# FPGA2_POWER.net
KiCad netlist of a schematic drawn in Altium Designer
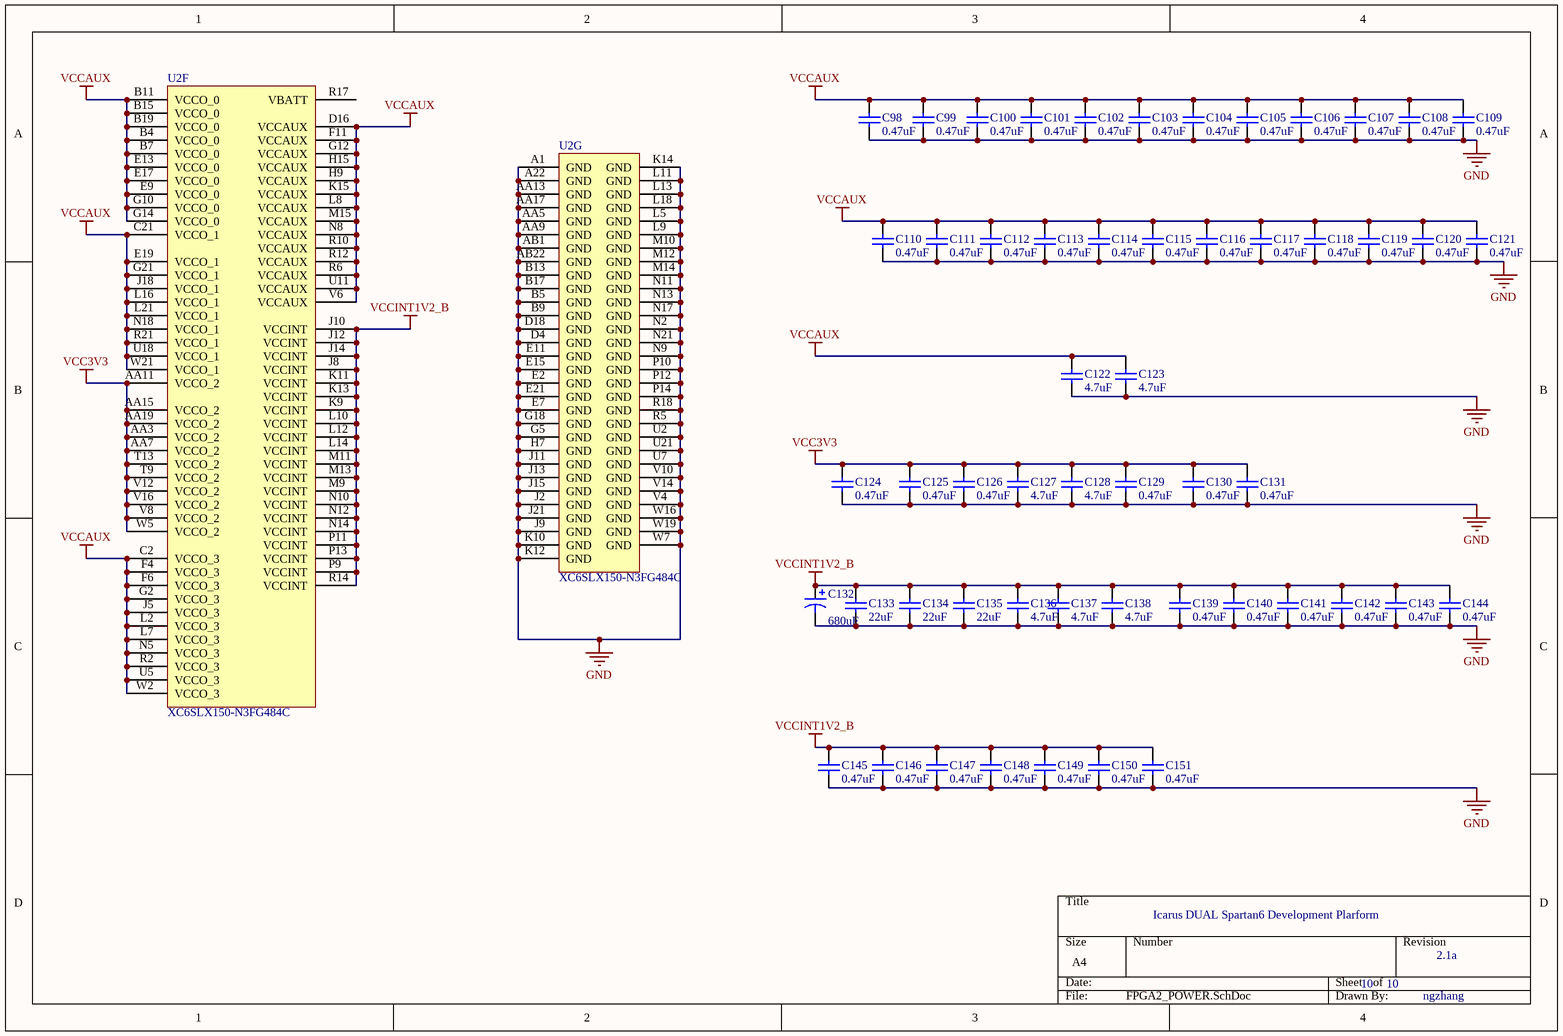
[diagram p0: FPGA2_POWER.SchDoc]

(export (version "E")
  (design (tool "Eeschema 10.0.6"))
  (components
    (comp (ref "C98")
      (value "0.47uF")
      (footprint "0402")
      (description "Capacitor (Semiconductor SIM Model)")
      (fields (field (name "PUBLISHER") "Altium Limited"))
      (libsource (lib "Miscellaneous Devices") (part "Cap Semi"))
    )
    (comp (ref "C99")
      (value "0.47uF")
      (footprint "0402")
      (description "Capacitor (Semiconductor SIM Model)")
      (fields (field (name "PUBLISHER") "Altium Limited"))
      (libsource (lib "Miscellaneous Devices") (part "Cap Semi"))
    )
    (comp (ref "C100")
      (value "0.47uF")
      (footprint "0402")
      (description "Capacitor (Semiconductor SIM Model)")
      (fields (field (name "PUBLISHER") "Altium Limited"))
      (libsource (lib "Miscellaneous Devices") (part "Cap Semi"))
    )
    (comp (ref "C101")
      (value "0.47uF")
      (footprint "0402")
      (description "Capacitor (Semiconductor SIM Model)")
      (fields (field (name "PUBLISHER") "Altium Limited"))
      (libsource (lib "Miscellaneous Devices") (part "Cap Semi"))
    )
    (comp (ref "C102")
      (value "0.47uF")
      (footprint "0402")
      (description "Capacitor (Semiconductor SIM Model)")
      (fields (field (name "PUBLISHER") "Altium Limited"))
      (libsource (lib "Miscellaneous Devices") (part "Cap Semi"))
    )
    (comp (ref "C103")
      (value "0.47uF")
      (footprint "0402")
      (description "Capacitor (Semiconductor SIM Model)")
      (fields (field (name "PUBLISHER") "Altium Limited"))
      (libsource (lib "Miscellaneous Devices") (part "Cap Semi"))
    )
    (comp (ref "C104")
      (value "0.47uF")
      (footprint "0402")
      (description "Capacitor (Semiconductor SIM Model)")
      (fields (field (name "PUBLISHER") "Altium Limited"))
      (libsource (lib "Miscellaneous Devices") (part "Cap Semi"))
    )
    (comp (ref "C105")
      (value "0.47uF")
      (footprint "0402")
      (description "Capacitor (Semiconductor SIM Model)")
      (fields (field (name "PUBLISHER") "Altium Limited"))
      (libsource (lib "Miscellaneous Devices") (part "Cap Semi"))
    )
    (comp (ref "C106")
      (value "0.47uF")
      (footprint "0402")
      (description "Capacitor (Semiconductor SIM Model)")
      (fields (field (name "PUBLISHER") "Altium Limited"))
      (libsource (lib "Miscellaneous Devices") (part "Cap Semi"))
    )
    (comp (ref "C107")
      (value "0.47uF")
      (footprint "0402")
      (description "Capacitor (Semiconductor SIM Model)")
      (fields (field (name "PUBLISHER") "Altium Limited"))
      (libsource (lib "Miscellaneous Devices") (part "Cap Semi"))
    )
    (comp (ref "C108")
      (value "0.47uF")
      (footprint "0402")
      (description "Capacitor (Semiconductor SIM Model)")
      (fields (field (name "PUBLISHER") "Altium Limited"))
      (libsource (lib "Miscellaneous Devices") (part "Cap Semi"))
    )
    (comp (ref "C109")
      (value "0.47uF")
      (footprint "0402")
      (description "Capacitor (Semiconductor SIM Model)")
      (fields (field (name "PUBLISHER") "Altium Limited"))
      (libsource (lib "Miscellaneous Devices") (part "Cap Semi"))
    )
    (comp (ref "C110")
      (value "0.47uF")
      (footprint "0402")
      (description "Capacitor (Semiconductor SIM Model)")
      (fields (field (name "PUBLISHER") "Altium Limited"))
      (libsource (lib "Miscellaneous Devices") (part "Cap Semi"))
    )
    (comp (ref "C111")
      (value "0.47uF")
      (footprint "0402")
      (description "Capacitor (Semiconductor SIM Model)")
      (fields (field (name "PUBLISHER") "Altium Limited"))
      (libsource (lib "Miscellaneous Devices") (part "Cap Semi"))
    )
    (comp (ref "C112")
      (value "0.47uF")
      (footprint "0402")
      (description "Capacitor (Semiconductor SIM Model)")
      (fields (field (name "PUBLISHER") "Altium Limited"))
      (libsource (lib "Miscellaneous Devices") (part "Cap Semi"))
    )
    (comp (ref "C113")
      (value "0.47uF")
      (footprint "0402")
      (description "Capacitor (Semiconductor SIM Model)")
      (fields (field (name "PUBLISHER") "Altium Limited"))
      (libsource (lib "Miscellaneous Devices") (part "Cap Semi"))
    )
    (comp (ref "C114")
      (value "0.47uF")
      (footprint "0402")
      (description "Capacitor (Semiconductor SIM Model)")
      (fields (field (name "PUBLISHER") "Altium Limited"))
      (libsource (lib "Miscellaneous Devices") (part "Cap Semi"))
    )
    (comp (ref "C115")
      (value "0.47uF")
      (footprint "0402")
      (description "Capacitor (Semiconductor SIM Model)")
      (fields (field (name "PUBLISHER") "Altium Limited"))
      (libsource (lib "Miscellaneous Devices") (part "Cap Semi"))
    )
    (comp (ref "C116")
      (value "0.47uF")
      (footprint "0402")
      (description "Capacitor (Semiconductor SIM Model)")
      (fields (field (name "PUBLISHER") "Altium Limited"))
      (libsource (lib "Miscellaneous Devices") (part "Cap Semi"))
    )
    (comp (ref "C117")
      (value "0.47uF")
      (footprint "0402")
      (description "Capacitor (Semiconductor SIM Model)")
      (fields (field (name "PUBLISHER") "Altium Limited"))
      (libsource (lib "Miscellaneous Devices") (part "Cap Semi"))
    )
    (comp (ref "C118")
      (value "0.47uF")
      (footprint "0402")
      (description "Capacitor (Semiconductor SIM Model)")
      (fields (field (name "PUBLISHER") "Altium Limited"))
      (libsource (lib "Miscellaneous Devices") (part "Cap Semi"))
    )
    (comp (ref "C119")
      (value "0.47uF")
      (footprint "0402")
      (description "Capacitor (Semiconductor SIM Model)")
      (fields (field (name "PUBLISHER") "Altium Limited"))
      (libsource (lib "Miscellaneous Devices") (part "Cap Semi"))
    )
    (comp (ref "C120")
      (value "0.47uF")
      (footprint "0402")
      (description "Capacitor (Semiconductor SIM Model)")
      (fields (field (name "PUBLISHER") "Altium Limited"))
      (libsource (lib "Miscellaneous Devices") (part "Cap Semi"))
    )
    (comp (ref "C121")
      (value "0.47uF")
      (footprint "0402")
      (description "Capacitor (Semiconductor SIM Model)")
      (fields (field (name "PUBLISHER") "Altium Limited"))
      (libsource (lib "Miscellaneous Devices") (part "Cap Semi"))
    )
    (comp (ref "C122")
      (value "4.7uF")
      (footprint "C0805")
      (description "Capacitor (Semiconductor SIM Model)")
      (fields (field (name "PUBLISHER") "Altium Limited"))
      (libsource (lib "Miscellaneous Devices") (part "Cap Semi"))
    )
    (comp (ref "C123")
      (value "4.7uF")
      (footprint "C0805")
      (description "Capacitor (Semiconductor SIM Model)")
      (fields (field (name "PUBLISHER") "Altium Limited"))
      (libsource (lib "Miscellaneous Devices") (part "Cap Semi"))
    )
    (comp (ref "C124")
      (value "0.47uF")
      (footprint "0402")
      (description "Capacitor (Semiconductor SIM Model)")
      (fields (field (name "PUBLISHER") "Altium Limited"))
      (libsource (lib "Miscellaneous Devices") (part "Cap Semi"))
    )
    (comp (ref "C125")
      (value "0.47uF")
      (footprint "0402")
      (description "Capacitor (Semiconductor SIM Model)")
      (fields (field (name "PUBLISHER") "Altium Limited"))
      (libsource (lib "Miscellaneous Devices") (part "Cap Semi"))
    )
    (comp (ref "C126")
      (value "0.47uF")
      (footprint "0402")
      (description "Capacitor (Semiconductor SIM Model)")
      (fields (field (name "PUBLISHER") "Altium Limited"))
      (libsource (lib "Miscellaneous Devices") (part "Cap Semi"))
    )
    (comp (ref "C127")
      (value "4.7uF")
      (footprint "C0805")
      (description "Capacitor (Semiconductor SIM Model)")
      (fields (field (name "PUBLISHER") "Altium Limited"))
      (libsource (lib "Miscellaneous Devices") (part "Cap Semi"))
    )
    (comp (ref "C128")
      (value "4.7uF")
      (footprint "C0805")
      (description "Capacitor (Semiconductor SIM Model)")
      (fields (field (name "PUBLISHER") "Altium Limited"))
      (libsource (lib "Miscellaneous Devices") (part "Cap Semi"))
    )
    (comp (ref "C129")
      (value "0.47uF")
      (footprint "0402")
      (description "Capacitor (Semiconductor SIM Model)")
      (fields (field (name "PUBLISHER") "Altium Limited"))
      (libsource (lib "Miscellaneous Devices") (part "Cap Semi"))
    )
    (comp (ref "C130")
      (value "0.47uF")
      (footprint "0402")
      (description "Capacitor (Semiconductor SIM Model)")
      (fields (field (name "PUBLISHER") "Altium Limited"))
      (libsource (lib "Miscellaneous Devices") (part "Cap Semi"))
    )
    (comp (ref "C131")
      (value "0.47uF")
      (footprint "0402")
      (description "Capacitor (Semiconductor SIM Model)")
      (fields (field (name "PUBLISHER") "Altium Limited"))
      (libsource (lib "Miscellaneous Devices") (part "Cap Semi"))
    )
    (comp (ref "C132")
      (value "680uF")
      (footprint "D")
      (description "Polarized Capacitor (Surface Mount)")
      (fields (field (name "PUBLISHER") "Altium Limited"))
      (libsource (lib "Miscellaneous Devices") (part "Cap Pol3"))
    )
    (comp (ref "C133")
      (value "22uF")
      (footprint "C1206")
      (description "Capacitor (Semiconductor SIM Model)")
      (fields (field (name "PUBLISHER") "Altium Limited"))
      (libsource (lib "Miscellaneous Devices") (part "Cap Semi"))
    )
    (comp (ref "C134")
      (value "22uF")
      (footprint "C1206")
      (description "Capacitor (Semiconductor SIM Model)")
      (fields (field (name "PUBLISHER") "Altium Limited"))
      (libsource (lib "Miscellaneous Devices") (part "Cap Semi"))
    )
    (comp (ref "C135")
      (value "22uF")
      (footprint "C1206")
      (description "Capacitor (Semiconductor SIM Model)")
      (fields (field (name "PUBLISHER") "Altium Limited"))
      (libsource (lib "Miscellaneous Devices") (part "Cap Semi"))
    )
    (comp (ref "C136")
      (value "4.7uF")
      (footprint "C0805")
      (description "Capacitor (Semiconductor SIM Model)")
      (fields (field (name "PUBLISHER") "Altium Limited"))
      (libsource (lib "Miscellaneous Devices") (part "Cap Semi"))
    )
    (comp (ref "C137")
      (value "4.7uF")
      (footprint "C0805")
      (description "Capacitor (Semiconductor SIM Model)")
      (fields (field (name "PUBLISHER") "Altium Limited"))
      (libsource (lib "Miscellaneous Devices") (part "Cap Semi"))
    )
    (comp (ref "C138")
      (value "4.7uF")
      (footprint "C0805")
      (description "Capacitor (Semiconductor SIM Model)")
      (fields (field (name "PUBLISHER") "Altium Limited"))
      (libsource (lib "Miscellaneous Devices") (part "Cap Semi"))
    )
    (comp (ref "C139")
      (value "0.47uF")
      (footprint "0402")
      (description "Capacitor (Semiconductor SIM Model)")
      (fields (field (name "PUBLISHER") "Altium Limited"))
      (libsource (lib "Miscellaneous Devices") (part "Cap Semi"))
    )
    (comp (ref "C140")
      (value "0.47uF")
      (footprint "0402")
      (description "Capacitor (Semiconductor SIM Model)")
      (fields (field (name "PUBLISHER") "Altium Limited"))
      (libsource (lib "Miscellaneous Devices") (part "Cap Semi"))
    )
    (comp (ref "C141")
      (value "0.47uF")
      (footprint "0402")
      (description "Capacitor (Semiconductor SIM Model)")
      (fields (field (name "PUBLISHER") "Altium Limited"))
      (libsource (lib "Miscellaneous Devices") (part "Cap Semi"))
    )
    (comp (ref "C142")
      (value "0.47uF")
      (footprint "0402")
      (description "Capacitor (Semiconductor SIM Model)")
      (fields (field (name "PUBLISHER") "Altium Limited"))
      (libsource (lib "Miscellaneous Devices") (part "Cap Semi"))
    )
    (comp (ref "C143")
      (value "0.47uF")
      (footprint "0402")
      (description "Capacitor (Semiconductor SIM Model)")
      (fields (field (name "PUBLISHER") "Altium Limited"))
      (libsource (lib "Miscellaneous Devices") (part "Cap Semi"))
    )
    (comp (ref "C144")
      (value "0.47uF")
      (footprint "0402")
      (description "Capacitor (Semiconductor SIM Model)")
      (fields (field (name "PUBLISHER") "Altium Limited"))
      (libsource (lib "Miscellaneous Devices") (part "Cap Semi"))
    )
    (comp (ref "C145")
      (value "0.47uF")
      (footprint "0402")
      (description "Capacitor (Semiconductor SIM Model)")
      (fields (field (name "PUBLISHER") "Altium Limited"))
      (libsource (lib "Miscellaneous Devices") (part "Cap Semi"))
    )
    (comp (ref "C146")
      (value "0.47uF")
      (footprint "0402")
      (description "Capacitor (Semiconductor SIM Model)")
      (fields (field (name "PUBLISHER") "Altium Limited"))
      (libsource (lib "Miscellaneous Devices") (part "Cap Semi"))
    )
    (comp (ref "C147")
      (value "0.47uF")
      (footprint "0402")
      (description "Capacitor (Semiconductor SIM Model)")
      (fields (field (name "PUBLISHER") "Altium Limited"))
      (libsource (lib "Miscellaneous Devices") (part "Cap Semi"))
    )
    (comp (ref "C148")
      (value "0.47uF")
      (footprint "0402")
      (description "Capacitor (Semiconductor SIM Model)")
      (fields (field (name "PUBLISHER") "Altium Limited"))
      (libsource (lib "Miscellaneous Devices") (part "Cap Semi"))
    )
    (comp (ref "C149")
      (value "0.47uF")
      (footprint "0402")
      (description "Capacitor (Semiconductor SIM Model)")
      (fields (field (name "PUBLISHER") "Altium Limited"))
      (libsource (lib "Miscellaneous Devices") (part "Cap Semi"))
    )
    (comp (ref "C150")
      (value "0.47uF")
      (footprint "0402")
      (description "Capacitor (Semiconductor SIM Model)")
      (fields (field (name "PUBLISHER") "Altium Limited"))
      (libsource (lib "Miscellaneous Devices") (part "Cap Semi"))
    )
    (comp (ref "C151")
      (value "0.47uF")
      (footprint "0402")
      (description "Capacitor (Semiconductor SIM Model)")
      (fields (field (name "PUBLISHER") "Altium Limited"))
      (libsource (lib "Miscellaneous Devices") (part "Cap Semi"))
    )
    (comp (ref "U2")
      (value "XC6SLX150-N3FG484C")
      (footprint "FG484")
      (fields (field (name "PUBLISHER") "Altium Limited"))
      (libsource (lib "Xilinx Spartan-6") (part "XC6SLX150-N3FG484C"))
    )
  )
  (nets
    (net (code "1") (name "GND") (class "Default")
      (node (ref "C100") (pin "1") (pinfunction "1_1") (pintype "passive"))
      (node (ref "C101") (pin "1") (pinfunction "1_1") (pintype "passive"))
      (node (ref "C102") (pin "1") (pinfunction "1_1") (pintype "passive"))
      (node (ref "C103") (pin "1") (pinfunction "1_1") (pintype "passive"))
      (node (ref "C104") (pin "1") (pinfunction "1_1") (pintype "passive"))
      (node (ref "C105") (pin "1") (pinfunction "1_1") (pintype "passive"))
      (node (ref "C106") (pin "1") (pinfunction "1_1") (pintype "passive"))
      (node (ref "C107") (pin "1") (pinfunction "1_1") (pintype "passive"))
      (node (ref "C108") (pin "1") (pinfunction "1_1") (pintype "passive"))
      (node (ref "C109") (pin "1") (pinfunction "1_1") (pintype "passive"))
      (node (ref "C110") (pin "1") (pinfunction "1_1") (pintype "passive"))
      (node (ref "C111") (pin "1") (pinfunction "1_1") (pintype "passive"))
      (node (ref "C112") (pin "1") (pinfunction "1_1") (pintype "passive"))
      (node (ref "C113") (pin "1") (pinfunction "1_1") (pintype "passive"))
      (node (ref "C114") (pin "1") (pinfunction "1_1") (pintype "passive"))
      (node (ref "C115") (pin "1") (pinfunction "1_1") (pintype "passive"))
      (node (ref "C116") (pin "1") (pinfunction "1_1") (pintype "passive"))
      (node (ref "C117") (pin "1") (pinfunction "1_1") (pintype "passive"))
      (node (ref "C118") (pin "1") (pinfunction "1_1") (pintype "passive"))
      (node (ref "C119") (pin "1") (pinfunction "1_1") (pintype "passive"))
      (node (ref "C120") (pin "1") (pinfunction "1_1") (pintype "passive"))
      (node (ref "C121") (pin "1") (pinfunction "1_1") (pintype "passive"))
      (node (ref "C122") (pin "1") (pinfunction "1_1") (pintype "passive"))
      (node (ref "C123") (pin "1") (pinfunction "1_1") (pintype "passive"))
      (node (ref "C124") (pin "1") (pinfunction "1_1") (pintype "passive"))
      (node (ref "C125") (pin "1") (pinfunction "1_1") (pintype "passive"))
      (node (ref "C126") (pin "1") (pinfunction "1_1") (pintype "passive"))
      (node (ref "C127") (pin "1") (pinfunction "1_1") (pintype "passive"))
      (node (ref "C128") (pin "1") (pinfunction "1_1") (pintype "passive"))
      (node (ref "C129") (pin "1") (pinfunction "1_1") (pintype "passive"))
      (node (ref "C130") (pin "1") (pinfunction "1_1") (pintype "passive"))
      (node (ref "C131") (pin "1") (pinfunction "1_1") (pintype "passive"))
      (node (ref "C132") (pin "2") (pinfunction "2_2") (pintype "passive"))
      (node (ref "C133") (pin "1") (pinfunction "1_1") (pintype "passive"))
      (node (ref "C134") (pin "1") (pinfunction "1_1") (pintype "passive"))
      (node (ref "C135") (pin "1") (pinfunction "1_1") (pintype "passive"))
      (node (ref "C136") (pin "1") (pinfunction "1_1") (pintype "passive"))
      (node (ref "C137") (pin "1") (pinfunction "1_1") (pintype "passive"))
      (node (ref "C138") (pin "1") (pinfunction "1_1") (pintype "passive"))
      (node (ref "C139") (pin "1") (pinfunction "1_1") (pintype "passive"))
      (node (ref "C140") (pin "1") (pinfunction "1_1") (pintype "passive"))
      (node (ref "C141") (pin "1") (pinfunction "1_1") (pintype "passive"))
      (node (ref "C142") (pin "1") (pinfunction "1_1") (pintype "passive"))
      (node (ref "C143") (pin "1") (pinfunction "1_1") (pintype "passive"))
      (node (ref "C144") (pin "1") (pinfunction "1_1") (pintype "passive"))
      (node (ref "C145") (pin "1") (pinfunction "1_1") (pintype "passive"))
      (node (ref "C146") (pin "1") (pinfunction "1_1") (pintype "passive"))
      (node (ref "C147") (pin "1") (pinfunction "1_1") (pintype "passive"))
      (node (ref "C148") (pin "1") (pinfunction "1_1") (pintype "passive"))
      (node (ref "C149") (pin "1") (pinfunction "1_1") (pintype "passive"))
      (node (ref "C150") (pin "1") (pinfunction "1_1") (pintype "passive"))
      (node (ref "C151") (pin "1") (pinfunction "1_1") (pintype "passive"))
      (node (ref "C98") (pin "1") (pinfunction "1_1") (pintype "passive"))
      (node (ref "C99") (pin "1") (pinfunction "1_1") (pintype "passive"))
      (node (ref "U2") (pin "A1") (pinfunction "GND_A1") (pintype "power_in"))
      (node (ref "U2") (pin "A22") (pinfunction "GND_A22") (pintype "power_in"))
      (node (ref "U2") (pin "AA13") (pinfunction "GND_AA13") (pintype "power_in"))
      (node (ref "U2") (pin "AA17") (pinfunction "GND_AA17") (pintype "power_in"))
      (node (ref "U2") (pin "AA5") (pinfunction "GND_AA5") (pintype "power_in"))
      (node (ref "U2") (pin "AA9") (pinfunction "GND_AA9") (pintype "power_in"))
      (node (ref "U2") (pin "AB1") (pinfunction "GND_AB1") (pintype "power_in"))
      (node (ref "U2") (pin "AB22") (pinfunction "GND_AB22") (pintype "power_in"))
      (node (ref "U2") (pin "B13") (pinfunction "GND_B13") (pintype "power_in"))
      (node (ref "U2") (pin "B17") (pinfunction "GND_B17") (pintype "power_in"))
      (node (ref "U2") (pin "B5") (pinfunction "GND_B5") (pintype "power_in"))
      (node (ref "U2") (pin "B9") (pinfunction "GND_B9") (pintype "power_in"))
      (node (ref "U2") (pin "D18") (pinfunction "GND_D18") (pintype "power_in"))
      (node (ref "U2") (pin "D4") (pinfunction "GND_D4") (pintype "power_in"))
      (node (ref "U2") (pin "E11") (pinfunction "GND_E11") (pintype "power_in"))
      (node (ref "U2") (pin "E15") (pinfunction "GND_E15") (pintype "power_in"))
      (node (ref "U2") (pin "E2") (pinfunction "GND_E2") (pintype "power_in"))
      (node (ref "U2") (pin "E21") (pinfunction "GND_E21") (pintype "power_in"))
      (node (ref "U2") (pin "E7") (pinfunction "GND_E7") (pintype "power_in"))
      (node (ref "U2") (pin "G18") (pinfunction "GND_G18") (pintype "power_in"))
      (node (ref "U2") (pin "G5") (pinfunction "GND_G5") (pintype "power_in"))
      (node (ref "U2") (pin "H7") (pinfunction "GND_H7") (pintype "power_in"))
      (node (ref "U2") (pin "J11") (pinfunction "GND_J11") (pintype "power_in"))
      (node (ref "U2") (pin "J13") (pinfunction "GND_J13") (pintype "power_in"))
      (node (ref "U2") (pin "J15") (pinfunction "GND_J15") (pintype "power_in"))
      (node (ref "U2") (pin "J2") (pinfunction "GND_J2") (pintype "power_in"))
      (node (ref "U2") (pin "J21") (pinfunction "GND_J21") (pintype "power_in"))
      (node (ref "U2") (pin "J9") (pinfunction "GND_J9") (pintype "power_in"))
      (node (ref "U2") (pin "K10") (pinfunction "GND_K10") (pintype "power_in"))
      (node (ref "U2") (pin "K12") (pinfunction "GND_K12") (pintype "power_in"))
      (node (ref "U2") (pin "K14") (pinfunction "GND_K14") (pintype "power_in"))
      (node (ref "U2") (pin "L11") (pinfunction "GND_L11") (pintype "power_in"))
      (node (ref "U2") (pin "L13") (pinfunction "GND_L13") (pintype "power_in"))
      (node (ref "U2") (pin "L18") (pinfunction "GND_L18") (pintype "power_in"))
      (node (ref "U2") (pin "L5") (pinfunction "GND_L5") (pintype "power_in"))
      (node (ref "U2") (pin "L9") (pinfunction "GND_L9") (pintype "power_in"))
      (node (ref "U2") (pin "M10") (pinfunction "GND_M10") (pintype "power_in"))
      (node (ref "U2") (pin "M12") (pinfunction "GND_M12") (pintype "power_in"))
      (node (ref "U2") (pin "M14") (pinfunction "GND_M14") (pintype "power_in"))
      (node (ref "U2") (pin "N11") (pinfunction "GND_N11") (pintype "power_in"))
      (node (ref "U2") (pin "N13") (pinfunction "GND_N13") (pintype "power_in"))
      (node (ref "U2") (pin "N17") (pinfunction "GND_N17") (pintype "power_in"))
      (node (ref "U2") (pin "N2") (pinfunction "GND_N2") (pintype "power_in"))
      (node (ref "U2") (pin "N21") (pinfunction "GND_N21") (pintype "power_in"))
      (node (ref "U2") (pin "N9") (pinfunction "GND_N9") (pintype "power_in"))
      (node (ref "U2") (pin "P10") (pinfunction "GND_P10") (pintype "power_in"))
      (node (ref "U2") (pin "P12") (pinfunction "GND_P12") (pintype "power_in"))
      (node (ref "U2") (pin "P14") (pinfunction "GND_P14") (pintype "power_in"))
      (node (ref "U2") (pin "R18") (pinfunction "GND_R18") (pintype "power_in"))
      (node (ref "U2") (pin "R5") (pinfunction "GND_R5") (pintype "power_in"))
      (node (ref "U2") (pin "U2") (pinfunction "GND_U2") (pintype "power_in"))
      (node (ref "U2") (pin "U21") (pinfunction "GND_U21") (pintype "power_in"))
      (node (ref "U2") (pin "U7") (pinfunction "GND_U7") (pintype "power_in"))
      (node (ref "U2") (pin "V10") (pinfunction "GND_V10") (pintype "power_in"))
      (node (ref "U2") (pin "V14") (pinfunction "GND_V14") (pintype "power_in"))
      (node (ref "U2") (pin "V4") (pinfunction "GND_V4") (pintype "power_in"))
      (node (ref "U2") (pin "W16") (pinfunction "GND_W16") (pintype "power_in"))
      (node (ref "U2") (pin "W19") (pinfunction "GND_W19") (pintype "power_in"))
      (node (ref "U2") (pin "W7") (pinfunction "GND_W7") (pintype "power_in"))
    )
    (net (code "2") (name "VCC3V3") (class "Default")
      (node (ref "C124") (pin "2") (pinfunction "2_2") (pintype "passive"))
      (node (ref "C125") (pin "2") (pinfunction "2_2") (pintype "passive"))
      (node (ref "C126") (pin "2") (pinfunction "2_2") (pintype "passive"))
      (node (ref "C127") (pin "2") (pinfunction "2_2") (pintype "passive"))
      (node (ref "C128") (pin "2") (pinfunction "2_2") (pintype "passive"))
      (node (ref "C129") (pin "2") (pinfunction "2_2") (pintype "passive"))
      (node (ref "C130") (pin "2") (pinfunction "2_2") (pintype "passive"))
      (node (ref "C131") (pin "2") (pinfunction "2_2") (pintype "passive"))
      (node (ref "U2") (pin "AA11") (pinfunction "VCCO_2_AA11") (pintype "power_in"))
      (node (ref "U2") (pin "AA15") (pinfunction "VCCO_2_AA15") (pintype "power_in"))
      (node (ref "U2") (pin "AA19") (pinfunction "VCCO_2_AA19") (pintype "power_in"))
      (node (ref "U2") (pin "AA3") (pinfunction "VCCO_2_AA3") (pintype "power_in"))
      (node (ref "U2") (pin "AA7") (pinfunction "VCCO_2_AA7") (pintype "power_in"))
      (node (ref "U2") (pin "T13") (pinfunction "VCCO_2_T13") (pintype "power_in"))
      (node (ref "U2") (pin "T9") (pinfunction "VCCO_2_T9") (pintype "power_in"))
      (node (ref "U2") (pin "V12") (pinfunction "VCCO_2_V12") (pintype "power_in"))
      (node (ref "U2") (pin "V16") (pinfunction "VCCO_2_V16") (pintype "power_in"))
      (node (ref "U2") (pin "V8") (pinfunction "VCCO_2_V8") (pintype "power_in"))
      (node (ref "U2") (pin "W5") (pinfunction "VCCO_2_W5") (pintype "power_in"))
    )
    (net (code "3") (name "VCCAUX") (class "Default")
      (node (ref "C100") (pin "2") (pinfunction "2_2") (pintype "passive"))
      (node (ref "C101") (pin "2") (pinfunction "2_2") (pintype "passive"))
      (node (ref "C102") (pin "2") (pinfunction "2_2") (pintype "passive"))
      (node (ref "C103") (pin "2") (pinfunction "2_2") (pintype "passive"))
      (node (ref "C104") (pin "2") (pinfunction "2_2") (pintype "passive"))
      (node (ref "C105") (pin "2") (pinfunction "2_2") (pintype "passive"))
      (node (ref "C106") (pin "2") (pinfunction "2_2") (pintype "passive"))
      (node (ref "C107") (pin "2") (pinfunction "2_2") (pintype "passive"))
      (node (ref "C108") (pin "2") (pinfunction "2_2") (pintype "passive"))
      (node (ref "C109") (pin "2") (pinfunction "2_2") (pintype "passive"))
      (node (ref "C110") (pin "2") (pinfunction "2_2") (pintype "passive"))
      (node (ref "C111") (pin "2") (pinfunction "2_2") (pintype "passive"))
      (node (ref "C112") (pin "2") (pinfunction "2_2") (pintype "passive"))
      (node (ref "C113") (pin "2") (pinfunction "2_2") (pintype "passive"))
      (node (ref "C114") (pin "2") (pinfunction "2_2") (pintype "passive"))
      (node (ref "C115") (pin "2") (pinfunction "2_2") (pintype "passive"))
      (node (ref "C116") (pin "2") (pinfunction "2_2") (pintype "passive"))
      (node (ref "C117") (pin "2") (pinfunction "2_2") (pintype "passive"))
      (node (ref "C118") (pin "2") (pinfunction "2_2") (pintype "passive"))
      (node (ref "C119") (pin "2") (pinfunction "2_2") (pintype "passive"))
      (node (ref "C120") (pin "2") (pinfunction "2_2") (pintype "passive"))
      (node (ref "C121") (pin "2") (pinfunction "2_2") (pintype "passive"))
      (node (ref "C122") (pin "2") (pinfunction "2_2") (pintype "passive"))
      (node (ref "C123") (pin "2") (pinfunction "2_2") (pintype "passive"))
      (node (ref "C98") (pin "2") (pinfunction "2_2") (pintype "passive"))
      (node (ref "C99") (pin "2") (pinfunction "2_2") (pintype "passive"))
      (node (ref "U2") (pin "B11") (pinfunction "VCCO_0_B11") (pintype "power_in"))
      (node (ref "U2") (pin "B15") (pinfunction "VCCO_0_B15") (pintype "power_in"))
      (node (ref "U2") (pin "B19") (pinfunction "VCCO_0_B19") (pintype "power_in"))
      (node (ref "U2") (pin "B4") (pinfunction "VCCO_0_B4") (pintype "power_in"))
      (node (ref "U2") (pin "B7") (pinfunction "VCCO_0_B7") (pintype "power_in"))
      (node (ref "U2") (pin "C2") (pinfunction "VCCO_3_C2") (pintype "power_in"))
      (node (ref "U2") (pin "C21") (pinfunction "VCCO_1_C21") (pintype "power_in"))
      (node (ref "U2") (pin "D16") (pinfunction "VCCAUX_D16") (pintype "power_in"))
      (node (ref "U2") (pin "E13") (pinfunction "VCCO_0_E13") (pintype "power_in"))
      (node (ref "U2") (pin "E17") (pinfunction "VCCO_0_E17") (pintype "power_in"))
      (node (ref "U2") (pin "E19") (pinfunction "VCCO_1_E19") (pintype "power_in"))
      (node (ref "U2") (pin "E9") (pinfunction "VCCO_0_E9") (pintype "power_in"))
      (node (ref "U2") (pin "F11") (pinfunction "VCCAUX_F11") (pintype "power_in"))
      (node (ref "U2") (pin "F4") (pinfunction "VCCO_3_F4") (pintype "power_in"))
      (node (ref "U2") (pin "F6") (pinfunction "VCCO_3_F6") (pintype "power_in"))
      (node (ref "U2") (pin "G10") (pinfunction "VCCO_0_G10") (pintype "power_in"))
      (node (ref "U2") (pin "G12") (pinfunction "VCCAUX_G12") (pintype "power_in"))
      (node (ref "U2") (pin "G14") (pinfunction "VCCO_0_G14") (pintype "power_in"))
      (node (ref "U2") (pin "G2") (pinfunction "VCCO_3_G2") (pintype "power_in"))
      (node (ref "U2") (pin "G21") (pinfunction "VCCO_1_G21") (pintype "power_in"))
      (node (ref "U2") (pin "H15") (pinfunction "VCCAUX_H15") (pintype "power_in"))
      (node (ref "U2") (pin "H9") (pinfunction "VCCAUX_H9") (pintype "power_in"))
      (node (ref "U2") (pin "J18") (pinfunction "VCCO_1_J18") (pintype "power_in"))
      (node (ref "U2") (pin "J5") (pinfunction "VCCO_3_J5") (pintype "power_in"))
      (node (ref "U2") (pin "K15") (pinfunction "VCCAUX_K15") (pintype "power_in"))
      (node (ref "U2") (pin "L16") (pinfunction "VCCO_1_L16") (pintype "power_in"))
      (node (ref "U2") (pin "L2") (pinfunction "VCCO_3_L2") (pintype "power_in"))
      (node (ref "U2") (pin "L21") (pinfunction "VCCO_1_L21") (pintype "power_in"))
      (node (ref "U2") (pin "L7") (pinfunction "VCCO_3_L7") (pintype "power_in"))
      (node (ref "U2") (pin "L8") (pinfunction "VCCAUX_L8") (pintype "power_in"))
      (node (ref "U2") (pin "M15") (pinfunction "VCCAUX_M15") (pintype "power_in"))
      (node (ref "U2") (pin "N18") (pinfunction "VCCO_1_N18") (pintype "power_in"))
      (node (ref "U2") (pin "N5") (pinfunction "VCCO_3_N5") (pintype "power_in"))
      (node (ref "U2") (pin "N8") (pinfunction "VCCAUX_N8") (pintype "power_in"))
      (node (ref "U2") (pin "R10") (pinfunction "VCCAUX_R10") (pintype "power_in"))
      (node (ref "U2") (pin "R12") (pinfunction "VCCAUX_R12") (pintype "power_in"))
      (node (ref "U2") (pin "R2") (pinfunction "VCCO_3_R2") (pintype "power_in"))
      (node (ref "U2") (pin "R21") (pinfunction "VCCO_1_R21") (pintype "power_in"))
      (node (ref "U2") (pin "R6") (pinfunction "VCCAUX_R6") (pintype "power_in"))
      (node (ref "U2") (pin "U11") (pinfunction "VCCAUX_U11") (pintype "power_in"))
      (node (ref "U2") (pin "U18") (pinfunction "VCCO_1_U18") (pintype "power_in"))
      (node (ref "U2") (pin "U5") (pinfunction "VCCO_3_U5") (pintype "power_in"))
      (node (ref "U2") (pin "V6") (pinfunction "VCCAUX_V6") (pintype "power_in"))
      (node (ref "U2") (pin "W2") (pinfunction "VCCO_3_W2") (pintype "power_in"))
      (node (ref "U2") (pin "W21") (pinfunction "VCCO_1_W21") (pintype "power_in"))
    )
    (net (code "4") (name "VCCINT1V2_B") (class "Default")
      (node (ref "C132") (pin "1") (pinfunction "1_1") (pintype "passive"))
      (node (ref "C133") (pin "2") (pinfunction "2_2") (pintype "passive"))
      (node (ref "C134") (pin "2") (pinfunction "2_2") (pintype "passive"))
      (node (ref "C135") (pin "2") (pinfunction "2_2") (pintype "passive"))
      (node (ref "C136") (pin "2") (pinfunction "2_2") (pintype "passive"))
      (node (ref "C137") (pin "2") (pinfunction "2_2") (pintype "passive"))
      (node (ref "C138") (pin "2") (pinfunction "2_2") (pintype "passive"))
      (node (ref "C139") (pin "2") (pinfunction "2_2") (pintype "passive"))
      (node (ref "C140") (pin "2") (pinfunction "2_2") (pintype "passive"))
      (node (ref "C141") (pin "2") (pinfunction "2_2") (pintype "passive"))
      (node (ref "C142") (pin "2") (pinfunction "2_2") (pintype "passive"))
      (node (ref "C143") (pin "2") (pinfunction "2_2") (pintype "passive"))
      (node (ref "C144") (pin "2") (pinfunction "2_2") (pintype "passive"))
      (node (ref "C145") (pin "2") (pinfunction "2_2") (pintype "passive"))
      (node (ref "C146") (pin "2") (pinfunction "2_2") (pintype "passive"))
      (node (ref "C147") (pin "2") (pinfunction "2_2") (pintype "passive"))
      (node (ref "C148") (pin "2") (pinfunction "2_2") (pintype "passive"))
      (node (ref "C149") (pin "2") (pinfunction "2_2") (pintype "passive"))
      (node (ref "C150") (pin "2") (pinfunction "2_2") (pintype "passive"))
      (node (ref "C151") (pin "2") (pinfunction "2_2") (pintype "passive"))
      (node (ref "U2") (pin "J10") (pinfunction "VCCINT_J10") (pintype "power_in"))
      (node (ref "U2") (pin "J12") (pinfunction "VCCINT_J12") (pintype "power_in"))
      (node (ref "U2") (pin "J14") (pinfunction "VCCINT_J14") (pintype "power_in"))
      (node (ref "U2") (pin "J8") (pinfunction "VCCINT_J8") (pintype "power_in"))
      (node (ref "U2") (pin "K11") (pinfunction "VCCINT_K11") (pintype "power_in"))
      (node (ref "U2") (pin "K13") (pinfunction "VCCINT_K13") (pintype "power_in"))
      (node (ref "U2") (pin "K9") (pinfunction "VCCINT_K9") (pintype "power_in"))
      (node (ref "U2") (pin "L10") (pinfunction "VCCINT_L10") (pintype "power_in"))
      (node (ref "U2") (pin "L12") (pinfunction "VCCINT_L12") (pintype "power_in"))
      (node (ref "U2") (pin "L14") (pinfunction "VCCINT_L14") (pintype "power_in"))
      (node (ref "U2") (pin "M11") (pinfunction "VCCINT_M11") (pintype "power_in"))
      (node (ref "U2") (pin "M13") (pinfunction "VCCINT_M13") (pintype "power_in"))
      (node (ref "U2") (pin "M9") (pinfunction "VCCINT_M9") (pintype "power_in"))
      (node (ref "U2") (pin "N10") (pinfunction "VCCINT_N10") (pintype "power_in"))
      (node (ref "U2") (pin "N12") (pinfunction "VCCINT_N12") (pintype "power_in"))
      (node (ref "U2") (pin "N14") (pinfunction "VCCINT_N14") (pintype "power_in"))
      (node (ref "U2") (pin "P11") (pinfunction "VCCINT_P11") (pintype "power_in"))
      (node (ref "U2") (pin "P13") (pinfunction "VCCINT_P13") (pintype "power_in"))
      (node (ref "U2") (pin "P9") (pinfunction "VCCINT_P9") (pintype "power_in"))
      (node (ref "U2") (pin "R14") (pinfunction "VCCINT_R14") (pintype "power_in"))
    )
    (net (code "5") (name "unconnected-(U2F-VBATT-PadR17)") (class "Default")
      (node (ref "U2") (pin "R17") (pinfunction "VBATT_R17") (pintype "power_in"))
    )
  )
)
